# BusControl.net
KiCad netlist of a schematic drawn in Altium Designer
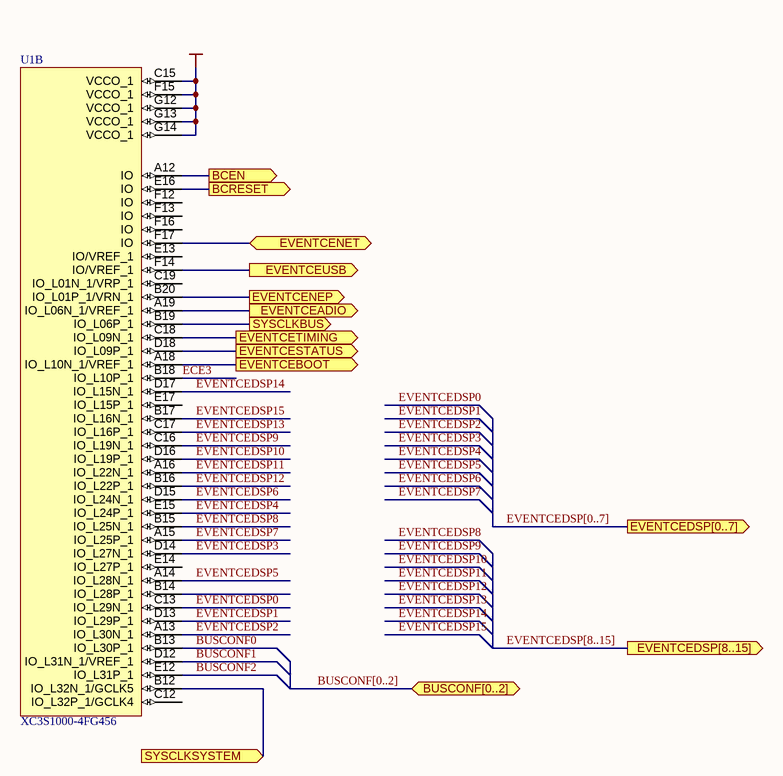
[diagram p0: BusControl.SCHDOC]

(export (version "E")
  (design (tool "Eeschema 10.0.6"))
  (components
    (comp (ref "U1")
      (value "XC3S1000-4FG456")
      (footprint "FG456")
      (description "Xilinx Spartan-3 FPGA")
      (libsource (lib "parts") (part "XC3S1000-4FG456"))
    )
  )
  (nets
    (net (code "1") (name "/BCEN") (class "Default")
      (node (ref "U1") (pin "A12") (pinfunction "IO_A12") (pintype "bidirectional"))
    )
    (net (code "2") (name "/BCRESET") (class "Default")
      (node (ref "U1") (pin "E16") (pinfunction "IO_E16") (pintype "bidirectional"))
    )
    (net (code "3") (name "/BUSCONF0") (class "Default")
      (node (ref "U1") (pin "B13") (pinfunction "IO_L30P_1_B13") (pintype "bidirectional"))
    )
    (net (code "4") (name "/BUSCONF1") (class "Default")
      (node (ref "U1") (pin "D12") (pinfunction "IO_L31N_1/VREF_1_D12") (pintype "bidirectional"))
    )
    (net (code "5") (name "/BUSCONF2") (class "Default")
      (node (ref "U1") (pin "E12") (pinfunction "IO_L31P_1_E12") (pintype "bidirectional"))
    )
    (net (code "7") (name "/ECE3") (class "Default")
      (node (ref "U1") (pin "B18") (pinfunction "IO_L10P_1_B18") (pintype "bidirectional"))
    )
    (net (code "8") (name "/EVENTCEADIO") (class "Default")
      (node (ref "U1") (pin "A19") (pinfunction "IO_L06N_1/VREF_1_A19") (pintype "bidirectional"))
    )
    (net (code "9") (name "/EVENTCEBOOT") (class "Default")
      (node (ref "U1") (pin "A18") (pinfunction "IO_L10N_1/VREF_1_A18") (pintype "bidirectional"))
    )
    (net (code "10") (name "/EVENTCEDSP0") (class "Default")
      (node (ref "U1") (pin "C13") (pinfunction "IO_L29N_1_C13") (pintype "bidirectional"))
    )
    (net (code "11") (name "/EVENTCEDSP1") (class "Default")
      (node (ref "U1") (pin "D13") (pinfunction "IO_L29P_1_D13") (pintype "bidirectional"))
    )
    (net (code "12") (name "/EVENTCEDSP2") (class "Default")
      (node (ref "U1") (pin "A13") (pinfunction "IO_L30N_1_A13") (pintype "bidirectional"))
    )
    (net (code "13") (name "/EVENTCEDSP3") (class "Default")
      (node (ref "U1") (pin "D14") (pinfunction "IO_L27N_1_D14") (pintype "bidirectional"))
    )
    (net (code "14") (name "/EVENTCEDSP4") (class "Default")
      (node (ref "U1") (pin "E15") (pinfunction "IO_L24P_1_E15") (pintype "bidirectional"))
    )
    (net (code "15") (name "/EVENTCEDSP5") (class "Default")
      (node (ref "U1") (pin "A14") (pinfunction "IO_L28N_1_A14") (pintype "bidirectional"))
    )
    (net (code "16") (name "/EVENTCEDSP6") (class "Default")
      (node (ref "U1") (pin "D15") (pinfunction "IO_L24N_1_D15") (pintype "bidirectional"))
    )
    (net (code "17") (name "/EVENTCEDSP7") (class "Default")
      (node (ref "U1") (pin "A15") (pinfunction "IO_L25P_1_A15") (pintype "bidirectional"))
    )
    (net (code "18") (name "/EVENTCEDSP8") (class "Default")
      (node (ref "U1") (pin "B15") (pinfunction "IO_L25N_1_B15") (pintype "bidirectional"))
    )
    (net (code "19") (name "/EVENTCEDSP9") (class "Default")
      (node (ref "U1") (pin "C16") (pinfunction "IO_L19N_1_C16") (pintype "bidirectional"))
    )
    (net (code "20") (name "/EVENTCEDSP10") (class "Default")
      (node (ref "U1") (pin "D16") (pinfunction "IO_L19P_1_D16") (pintype "bidirectional"))
    )
    (net (code "21") (name "/EVENTCEDSP11") (class "Default")
      (node (ref "U1") (pin "A16") (pinfunction "IO_L22N_1_A16") (pintype "bidirectional"))
    )
    (net (code "22") (name "/EVENTCEDSP12") (class "Default")
      (node (ref "U1") (pin "B16") (pinfunction "IO_L22P_1_B16") (pintype "bidirectional"))
    )
    (net (code "23") (name "/EVENTCEDSP13") (class "Default")
      (node (ref "U1") (pin "C17") (pinfunction "IO_L16P_1_C17") (pintype "bidirectional"))
    )
    (net (code "24") (name "/EVENTCEDSP14") (class "Default")
      (node (ref "U1") (pin "D17") (pinfunction "IO_L15N_1_D17") (pintype "bidirectional"))
    )
    (net (code "25") (name "/EVENTCEDSP15") (class "Default")
      (node (ref "U1") (pin "B17") (pinfunction "IO_L16N_1_B17") (pintype "bidirectional"))
    )
    (net (code "28") (name "/EVENTCENEP") (class "Default")
      (node (ref "U1") (pin "B20") (pinfunction "IO_L01P_1/VRN_1_B20") (pintype "bidirectional"))
    )
    (net (code "29") (name "/EVENTCENET") (class "Default")
      (node (ref "U1") (pin "F17") (pinfunction "IO_F17") (pintype "bidirectional"))
    )
    (net (code "30") (name "/EVENTCESTATUS") (class "Default")
      (node (ref "U1") (pin "D18") (pinfunction "IO_L09P_1_D18") (pintype "bidirectional"))
    )
    (net (code "31") (name "/EVENTCETIMING") (class "Default")
      (node (ref "U1") (pin "C18") (pinfunction "IO_L09N_1_C18") (pintype "bidirectional"))
    )
    (net (code "32") (name "/EVENTCEUSB") (class "Default")
      (node (ref "U1") (pin "F14") (pinfunction "IO/VREF_1_F14") (pintype "bidirectional"))
    )
    (net (code "33") (name "/SYSCLKBUS") (class "Default")
      (node (ref "U1") (pin "B19") (pinfunction "IO_L06P_1_B19") (pintype "bidirectional"))
    )
    (net (code "34") (name "/SYSCLKSYSTEM") (class "Default")
      (node (ref "U1") (pin "B12") (pinfunction "IO_L32N_1/GCLK5_B12") (pintype "bidirectional"))
    )
    (net (code "35") (name "VCC") (class "Default")
      (node (ref "U1") (pin "C15") (pinfunction "VCCO_1_C15") (pintype "bidirectional"))
      (node (ref "U1") (pin "F15") (pinfunction "VCCO_1_F15") (pintype "bidirectional"))
      (node (ref "U1") (pin "G12") (pinfunction "VCCO_1_G12") (pintype "bidirectional"))
      (node (ref "U1") (pin "G13") (pinfunction "VCCO_1_G13") (pintype "bidirectional"))
      (node (ref "U1") (pin "G14") (pinfunction "VCCO_1_G14") (pintype "bidirectional"))
    )
    (net (code "36") (name "unconnected-(U1B-IO-PadF12)") (class "Default")
      (node (ref "U1") (pin "F12") (pinfunction "IO_F12") (pintype "bidirectional"))
    )
    (net (code "37") (name "unconnected-(U1B-IO-PadF13)") (class "Default")
      (node (ref "U1") (pin "F13") (pinfunction "IO_F13") (pintype "bidirectional"))
    )
    (net (code "38") (name "unconnected-(U1B-IO-PadF16)") (class "Default")
      (node (ref "U1") (pin "F16") (pinfunction "IO_F16") (pintype "bidirectional"))
    )
    (net (code "39") (name "unconnected-(U1B-IO_L01N_1{slash}VRP_1-PadC19)") (class "Default")
      (node (ref "U1") (pin "C19") (pinfunction "IO_L01N_1/VRP_1_C19") (pintype "bidirectional"))
    )
    (net (code "40") (name "unconnected-(U1B-IO_L15P_1-PadE17)") (class "Default")
      (node (ref "U1") (pin "E17") (pinfunction "IO_L15P_1_E17") (pintype "bidirectional"))
    )
    (net (code "41") (name "unconnected-(U1B-IO_L27P_1-PadE14)") (class "Default")
      (node (ref "U1") (pin "E14") (pinfunction "IO_L27P_1_E14") (pintype "bidirectional"))
    )
    (net (code "42") (name "unconnected-(U1B-IO_L28P_1-PadB14)") (class "Default")
      (node (ref "U1") (pin "B14") (pinfunction "IO_L28P_1_B14") (pintype "bidirectional"))
    )
    (net (code "43") (name "unconnected-(U1B-IO_L32P_1{slash}GCLK4-PadC12)") (class "Default")
      (node (ref "U1") (pin "C12") (pinfunction "IO_L32P_1/GCLK4_C12") (pintype "bidirectional"))
    )
    (net (code "44") (name "unconnected-(U1B-IO{slash}VREF_1-PadE13)") (class "Default")
      (node (ref "U1") (pin "E13") (pinfunction "IO/VREF_1_E13") (pintype "bidirectional"))
    )
  )
)
